# MODULO2_ps.net
KiCad netlist of a schematic drawn in EAGLE
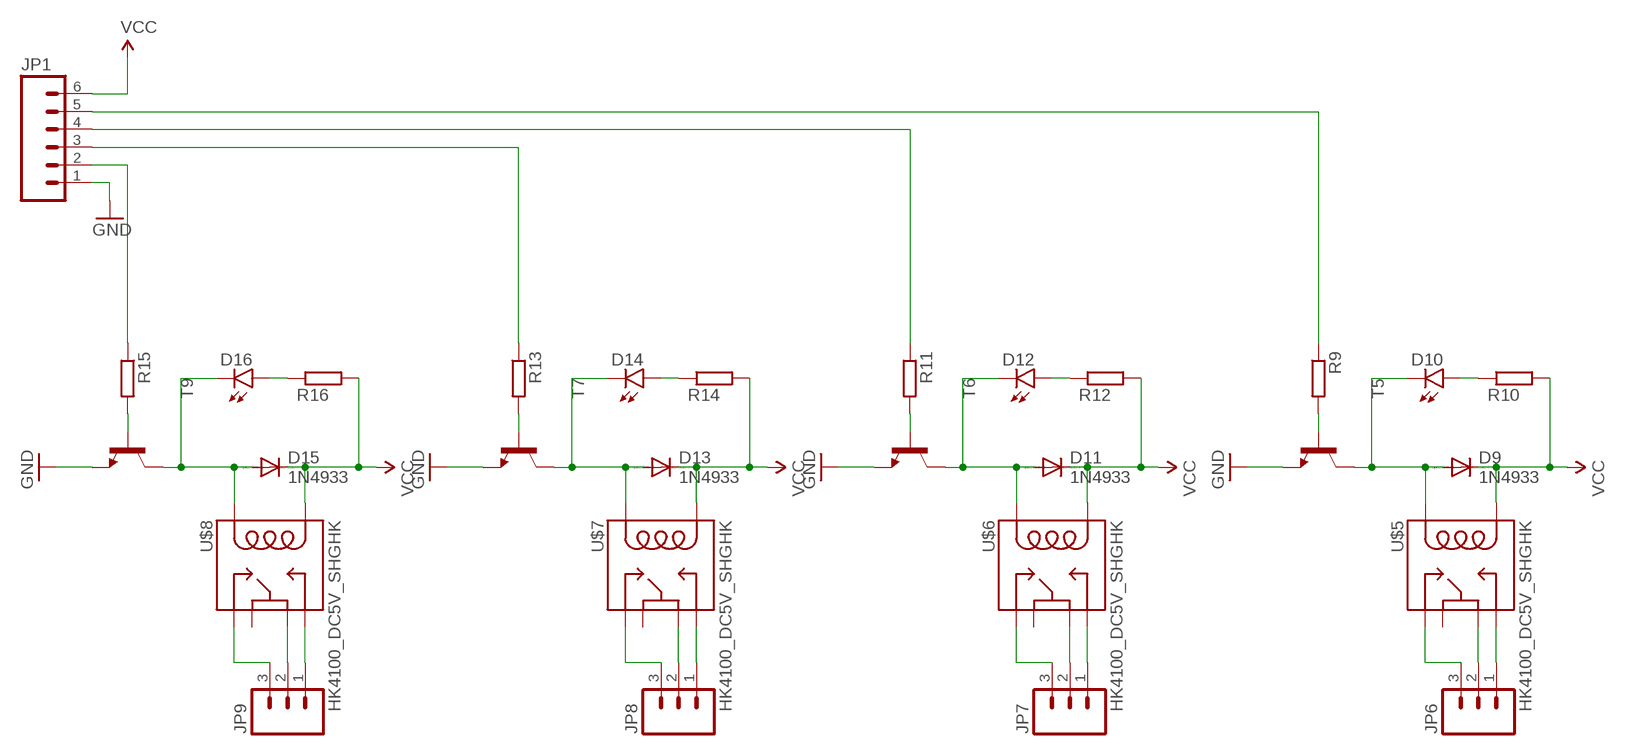
[diagram p0: schematic, sheet 1]

(export (version "E")
  (design (tool "Eeschema 10.0.6"))
  (components
    (comp (ref "D9")
      (value "1N4933")
      (footprint "eagle-import:DO41-10")
      (libsource (lib "eagle-import") (part "1N4933"))
    )
    (comp (ref "D10")
      (value "LED5MM")
      (footprint "eagle-import:LED5MM")
      (libsource (lib "eagle-import") (part "LED5MM"))
    )
    (comp (ref "D11")
      (value "1N4933")
      (footprint "eagle-import:DO41-10")
      (libsource (lib "eagle-import") (part "1N4933"))
    )
    (comp (ref "D12")
      (value "LED5MM")
      (footprint "eagle-import:LED5MM")
      (libsource (lib "eagle-import") (part "LED5MM"))
    )
    (comp (ref "D13")
      (value "1N4933")
      (footprint "eagle-import:DO41-10")
      (libsource (lib "eagle-import") (part "1N4933"))
    )
    (comp (ref "D14")
      (value "LED5MM")
      (footprint "eagle-import:LED5MM")
      (libsource (lib "eagle-import") (part "LED5MM"))
    )
    (comp (ref "D15")
      (value "1N4933")
      (footprint "eagle-import:DO41-10")
      (libsource (lib "eagle-import") (part "1N4933"))
    )
    (comp (ref "D16")
      (value "LED5MM")
      (footprint "eagle-import:LED5MM")
      (libsource (lib "eagle-import") (part "LED5MM"))
    )
    (comp (ref "JP1")
      (value "M06SILK_FEMALE_PTH")
      (footprint "eagle-import:1X06")
      (libsource (lib "eagle-import") (part "M06SILK_FEMALE_PTH"))
    )
    (comp (ref "JP6")
      (value "M03-SCREW-5MM")
      (footprint "eagle-import:SCREWTERMINAL-5MM-3")
      (libsource (lib "eagle-import") (part "M03-SCREW-5MM"))
    )
    (comp (ref "JP7")
      (value "M03-SCREW-5MM")
      (footprint "eagle-import:SCREWTERMINAL-5MM-3")
      (libsource (lib "eagle-import") (part "M03-SCREW-5MM"))
    )
    (comp (ref "JP8")
      (value "M03-SCREW-5MM")
      (footprint "eagle-import:SCREWTERMINAL-5MM-3")
      (libsource (lib "eagle-import") (part "M03-SCREW-5MM"))
    )
    (comp (ref "JP9")
      (value "M03-SCREW-5MM")
      (footprint "eagle-import:SCREWTERMINAL-5MM-3")
      (libsource (lib "eagle-import") (part "M03-SCREW-5MM"))
    )
    (comp (ref "R9")
      (value "R-EU_R0805")
      (footprint "eagle-import:R0805")
      (libsource (lib "eagle-import") (part "R-EU_R0805"))
    )
    (comp (ref "R10")
      (value "R-EU_R0805")
      (footprint "eagle-import:R0805")
      (libsource (lib "eagle-import") (part "R-EU_R0805"))
    )
    (comp (ref "R11")
      (value "R-EU_R0805")
      (footprint "eagle-import:R0805")
      (libsource (lib "eagle-import") (part "R-EU_R0805"))
    )
    (comp (ref "R12")
      (value "R-EU_R0805")
      (footprint "eagle-import:R0805")
      (libsource (lib "eagle-import") (part "R-EU_R0805"))
    )
    (comp (ref "R13")
      (value "R-EU_R0805")
      (footprint "eagle-import:R0805")
      (libsource (lib "eagle-import") (part "R-EU_R0805"))
    )
    (comp (ref "R14")
      (value "R-EU_R0805")
      (footprint "eagle-import:R0805")
      (libsource (lib "eagle-import") (part "R-EU_R0805"))
    )
    (comp (ref "R15")
      (value "R-EU_R0805")
      (footprint "eagle-import:R0805")
      (libsource (lib "eagle-import") (part "R-EU_R0805"))
    )
    (comp (ref "R16")
      (value "R-EU_R0805")
      (footprint "eagle-import:R0805")
      (libsource (lib "eagle-import") (part "R-EU_R0805"))
    )
    (comp (ref "T5")
      (value "-NPN-TO92-EBC")
      (footprint "eagle-import:TO92-EBC")
      (libsource (lib "eagle-import") (part "-NPN-TO92-EBC"))
    )
    (comp (ref "T6")
      (value "-NPN-TO92-EBC")
      (footprint "eagle-import:TO92-EBC")
      (libsource (lib "eagle-import") (part "-NPN-TO92-EBC"))
    )
    (comp (ref "T7")
      (value "-NPN-TO92-EBC")
      (footprint "eagle-import:TO92-EBC")
      (libsource (lib "eagle-import") (part "-NPN-TO92-EBC"))
    )
    (comp (ref "T9")
      (value "-NPN-TO92-EBC")
      (footprint "eagle-import:TO92-EBC")
      (libsource (lib "eagle-import") (part "-NPN-TO92-EBC"))
    )
    (comp (ref "U$5")
      (value "HK4100_DC5V_SHGHK")
      (footprint "eagle-import:HK4100")
      (libsource (lib "eagle-import") (part "HK4100_DC5V_SHGHK"))
    )
    (comp (ref "U$6")
      (value "HK4100_DC5V_SHGHK")
      (footprint "eagle-import:HK4100")
      (libsource (lib "eagle-import") (part "HK4100_DC5V_SHGHK"))
    )
    (comp (ref "U$7")
      (value "HK4100_DC5V_SHGHK")
      (footprint "eagle-import:HK4100")
      (libsource (lib "eagle-import") (part "HK4100_DC5V_SHGHK"))
    )
    (comp (ref "U$8")
      (value "HK4100_DC5V_SHGHK")
      (footprint "eagle-import:HK4100")
      (libsource (lib "eagle-import") (part "HK4100_DC5V_SHGHK"))
    )
  )
  (nets
    (net (code "1") (name "GND") (class "Default")
      (node (ref "JP1") (pin "1") (pinfunction "1_1") (pintype "passive"))
      (node (ref "T5") (pin "E") (pinfunction "E_E") (pintype "passive"))
      (node (ref "T6") (pin "E") (pinfunction "E_E") (pintype "passive"))
      (node (ref "T7") (pin "E") (pinfunction "E_E") (pintype "passive"))
      (node (ref "T9") (pin "E") (pinfunction "E_E") (pintype "passive"))
    )
    (net (code "2") (name "Net-(D10-C)") (class "Default")
      (node (ref "D10") (pin "K") (pinfunction "C_K") (pintype "passive"))
      (node (ref "D9") (pin "A") (pinfunction "A_A") (pintype "passive"))
      (node (ref "T5") (pin "C") (pinfunction "C_C") (pintype "passive"))
      (node (ref "U$5") (pin "6") (pinfunction "2_6") (pintype "bidirectional"))
    )
    (net (code "3") (name "Net-(D10-PadA)") (class "Default")
      (node (ref "D10") (pin "A") (pinfunction "A_A") (pintype "passive"))
      (node (ref "R10") (pin "1") (pinfunction "1_1") (pintype "passive"))
    )
    (net (code "4") (name "Net-(D12-C)") (class "Default")
      (node (ref "D11") (pin "A") (pinfunction "A_A") (pintype "passive"))
      (node (ref "D12") (pin "K") (pinfunction "C_K") (pintype "passive"))
      (node (ref "T6") (pin "C") (pinfunction "C_C") (pintype "passive"))
      (node (ref "U$6") (pin "6") (pinfunction "2_6") (pintype "bidirectional"))
    )
    (net (code "5") (name "Net-(D12-PadA)") (class "Default")
      (node (ref "D12") (pin "A") (pinfunction "A_A") (pintype "passive"))
      (node (ref "R12") (pin "1") (pinfunction "1_1") (pintype "passive"))
    )
    (net (code "6") (name "Net-(D14-C)") (class "Default")
      (node (ref "D13") (pin "A") (pinfunction "A_A") (pintype "passive"))
      (node (ref "D14") (pin "K") (pinfunction "C_K") (pintype "passive"))
      (node (ref "T7") (pin "C") (pinfunction "C_C") (pintype "passive"))
      (node (ref "U$7") (pin "6") (pinfunction "2_6") (pintype "bidirectional"))
    )
    (net (code "7") (name "Net-(D14-PadA)") (class "Default")
      (node (ref "D14") (pin "A") (pinfunction "A_A") (pintype "passive"))
      (node (ref "R14") (pin "1") (pinfunction "1_1") (pintype "passive"))
    )
    (net (code "8") (name "Net-(D16-C)") (class "Default")
      (node (ref "D15") (pin "A") (pinfunction "A_A") (pintype "passive"))
      (node (ref "D16") (pin "K") (pinfunction "C_K") (pintype "passive"))
      (node (ref "T9") (pin "C") (pinfunction "C_C") (pintype "passive"))
      (node (ref "U$8") (pin "6") (pinfunction "2_6") (pintype "bidirectional"))
    )
    (net (code "9") (name "Net-(D16-PadA)") (class "Default")
      (node (ref "D16") (pin "A") (pinfunction "A_A") (pintype "passive"))
      (node (ref "R16") (pin "1") (pinfunction "1_1") (pintype "passive"))
    )
    (net (code "10") (name "Net-(JP1-Pad2)") (class "Default")
      (node (ref "JP1") (pin "2") (pinfunction "2_2") (pintype "passive"))
      (node (ref "R15") (pin "1") (pinfunction "1_1") (pintype "passive"))
    )
    (net (code "11") (name "Net-(JP1-Pad3)") (class "Default")
      (node (ref "JP1") (pin "3") (pinfunction "3_3") (pintype "passive"))
      (node (ref "R13") (pin "1") (pinfunction "1_1") (pintype "passive"))
    )
    (net (code "12") (name "Net-(JP1-Pad4)") (class "Default")
      (node (ref "JP1") (pin "4") (pinfunction "4_4") (pintype "passive"))
      (node (ref "R11") (pin "1") (pinfunction "1_1") (pintype "passive"))
    )
    (net (code "13") (name "Net-(JP1-Pad5)") (class "Default")
      (node (ref "JP1") (pin "5") (pinfunction "5_5") (pintype "passive"))
      (node (ref "R9") (pin "1") (pinfunction "1_1") (pintype "passive"))
    )
    (net (code "14") (name "Net-(R9-Pad2)") (class "Default")
      (node (ref "R9") (pin "2") (pinfunction "2_2") (pintype "passive"))
      (node (ref "T5") (pin "B") (pinfunction "B_B") (pintype "passive"))
    )
    (net (code "15") (name "Net-(R11-Pad2)") (class "Default")
      (node (ref "R11") (pin "2") (pinfunction "2_2") (pintype "passive"))
      (node (ref "T6") (pin "B") (pinfunction "B_B") (pintype "passive"))
    )
    (net (code "16") (name "Net-(R13-Pad2)") (class "Default")
      (node (ref "R13") (pin "2") (pinfunction "2_2") (pintype "passive"))
      (node (ref "T7") (pin "B") (pinfunction "B_B") (pintype "passive"))
    )
    (net (code "17") (name "Net-(R15-Pad2)") (class "Default")
      (node (ref "R15") (pin "2") (pinfunction "2_2") (pintype "passive"))
      (node (ref "T9") (pin "B") (pinfunction "B_B") (pintype "passive"))
    )
    (net (code "18") (name "Net-(U$5-1)") (class "Default")
      (node (ref "JP6") (pin "3") (pinfunction "3_3") (pintype "passive"))
      (node (ref "U$5") (pin "7") (pinfunction "1_7") (pintype "bidirectional"))
    )
    (net (code "19") (name "Net-(U$5-6)") (class "Default")
      (node (ref "JP6") (pin "2") (pinfunction "2_2") (pintype "passive"))
      (node (ref "U$5") (pin "14") (pinfunction "6_14") (pintype "bidirectional"))
    )
    (net (code "20") (name "Net-(U$5-10)") (class "Default")
      (node (ref "JP6") (pin "1") (pinfunction "1_1") (pintype "passive"))
      (node (ref "U$5") (pin "8") (pinfunction "10_8") (pintype "bidirectional"))
    )
    (net (code "21") (name "Net-(U$6-1)") (class "Default")
      (node (ref "JP7") (pin "3") (pinfunction "3_3") (pintype "passive"))
      (node (ref "U$6") (pin "7") (pinfunction "1_7") (pintype "bidirectional"))
    )
    (net (code "22") (name "Net-(U$6-6)") (class "Default")
      (node (ref "JP7") (pin "2") (pinfunction "2_2") (pintype "passive"))
      (node (ref "U$6") (pin "14") (pinfunction "6_14") (pintype "bidirectional"))
    )
    (net (code "23") (name "Net-(U$6-10)") (class "Default")
      (node (ref "JP7") (pin "1") (pinfunction "1_1") (pintype "passive"))
      (node (ref "U$6") (pin "8") (pinfunction "10_8") (pintype "bidirectional"))
    )
    (net (code "24") (name "Net-(U$7-1)") (class "Default")
      (node (ref "JP8") (pin "3") (pinfunction "3_3") (pintype "passive"))
      (node (ref "U$7") (pin "7") (pinfunction "1_7") (pintype "bidirectional"))
    )
    (net (code "25") (name "Net-(U$7-6)") (class "Default")
      (node (ref "JP8") (pin "2") (pinfunction "2_2") (pintype "passive"))
      (node (ref "U$7") (pin "14") (pinfunction "6_14") (pintype "bidirectional"))
    )
    (net (code "26") (name "Net-(U$7-10)") (class "Default")
      (node (ref "JP8") (pin "1") (pinfunction "1_1") (pintype "passive"))
      (node (ref "U$7") (pin "8") (pinfunction "10_8") (pintype "bidirectional"))
    )
    (net (code "27") (name "Net-(U$8-1)") (class "Default")
      (node (ref "JP9") (pin "3") (pinfunction "3_3") (pintype "passive"))
      (node (ref "U$8") (pin "7") (pinfunction "1_7") (pintype "bidirectional"))
    )
    (net (code "28") (name "Net-(U$8-6)") (class "Default")
      (node (ref "JP9") (pin "2") (pinfunction "2_2") (pintype "passive"))
      (node (ref "U$8") (pin "14") (pinfunction "6_14") (pintype "bidirectional"))
    )
    (net (code "29") (name "Net-(U$8-10)") (class "Default")
      (node (ref "JP9") (pin "1") (pinfunction "1_1") (pintype "passive"))
      (node (ref "U$8") (pin "8") (pinfunction "10_8") (pintype "bidirectional"))
    )
    (net (code "30") (name "VCC") (class "Default")
      (node (ref "D11") (pin "C") (pinfunction "C_C") (pintype "passive"))
      (node (ref "D13") (pin "C") (pinfunction "C_C") (pintype "passive"))
      (node (ref "D15") (pin "C") (pinfunction "C_C") (pintype "passive"))
      (node (ref "D9") (pin "C") (pinfunction "C_C") (pintype "passive"))
      (node (ref "JP1") (pin "6") (pinfunction "6_6") (pintype "passive"))
      (node (ref "R10") (pin "2") (pinfunction "2_2") (pintype "passive"))
      (node (ref "R12") (pin "2") (pinfunction "2_2") (pintype "passive"))
      (node (ref "R14") (pin "2") (pinfunction "2_2") (pintype "passive"))
      (node (ref "R16") (pin "2") (pinfunction "2_2") (pintype "passive"))
      (node (ref "U$5") (pin "9") (pinfunction "9_9") (pintype "bidirectional"))
      (node (ref "U$6") (pin "9") (pinfunction "9_9") (pintype "bidirectional"))
      (node (ref "U$7") (pin "9") (pinfunction "9_9") (pintype "bidirectional"))
      (node (ref "U$8") (pin "9") (pinfunction "9_9") (pintype "bidirectional"))
    )
    (net (code "31") (name "unconnected-(U$5-5-Pad1)") (class "Default")
      (node (ref "U$5") (pin "1") (pinfunction "5_1") (pintype "bidirectional"))
    )
    (net (code "32") (name "unconnected-(U$6-5-Pad1)") (class "Default")
      (node (ref "U$6") (pin "1") (pinfunction "5_1") (pintype "bidirectional"))
    )
    (net (code "33") (name "unconnected-(U$7-5-Pad1)") (class "Default")
      (node (ref "U$7") (pin "1") (pinfunction "5_1") (pintype "bidirectional"))
    )
    (net (code "34") (name "unconnected-(U$8-5-Pad1)") (class "Default")
      (node (ref "U$8") (pin "1") (pinfunction "5_1") (pintype "bidirectional"))
    )
  )
)
